# Mobile_Robot_Remote_Controller.net
KiCad netlist of a schematic drawn in Altium Designer
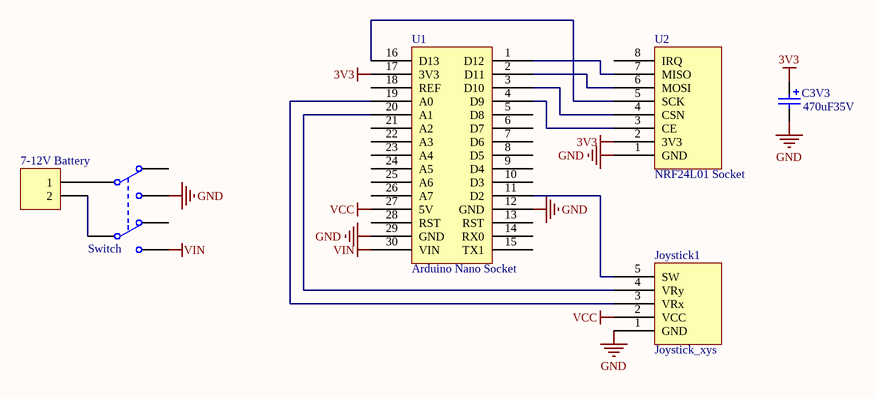
[diagram p0: Mobile Robot Remote Controller.SchDoc]

(export (version "E")
  (design (tool "Eeschema 10.0.6"))
  (components
    (comp (ref "7-12V Battery")
      (value "Header 2")
      (footprint "KF301-2P")
      (libsource (lib "Customer_Library") (part "Header 2"))
    )
    (comp (ref "C3V3")
      (value "470uF35V")
      (footprint "cp10x10")
      (fields (field (name "Comment") "Cap Pol"))
      (libsource (lib "Customer_Library") (part "Cap Pol"))
    )
    (comp (ref "Joystick1")
      (value "Joystick_xys")
      (footprint "Joystick_xys")
      (libsource (lib "Customer_Library") (part "Joystick_xys"))
    )
    (comp (ref "Switch")
      (value "Push Switch")
      (footprint "Push Switch 7x7")
      (libsource (lib "Customer_Library") (part "Push Switch"))
    )
    (comp (ref "U1")
      (value "Arduino Nano Socket")
      (footprint "arduino nano socket")
      (libsource (lib "Customer_Library") (part "Arduino Nano Socket"))
    )
    (comp (ref "U2")
      (value "NRF24L01 Socket")
      (footprint "nrf24l01 socket")
      (libsource (lib "Customer_Library") (part "NRF24L01 Socket"))
    )
  )
  (nets
    (net (code "1") (name "3V3") (class "Default")
      (node (ref "C3V3") (pin "1") (pinfunction "1_1") (pintype "passive"))
      (node (ref "U1") (pin "17") (pinfunction "3V3_17") (pintype "passive"))
      (node (ref "U2") (pin "2") (pinfunction "3V3_2") (pintype "passive"))
    )
    (net (code "2") (name "GND") (class "Default")
      (node (ref "C3V3") (pin "2") (pinfunction "2_2") (pintype "passive"))
      (node (ref "Joystick1") (pin "1") (pinfunction "GND_1") (pintype "passive"))
      (node (ref "Switch") (pin "3") (pinfunction "NO1_3") (pintype "passive"))
      (node (ref "U1") (pin "12") (pinfunction "GND_12") (pintype "passive"))
      (node (ref "U1") (pin "29") (pinfunction "GND_29") (pintype "passive"))
      (node (ref "U2") (pin "1") (pinfunction "GND_1") (pintype "passive"))
    )
    (net (code "3") (name "Net-(Joystick1-SW)") (class "Default")
      (node (ref "Joystick1") (pin "5") (pinfunction "SW_5") (pintype "passive"))
      (node (ref "U1") (pin "11") (pinfunction "D2_11") (pintype "passive"))
    )
    (net (code "4") (name "Net-(Joystick1-VRx)") (class "Default")
      (node (ref "Joystick1") (pin "3") (pinfunction "VRx_3") (pintype "passive"))
      (node (ref "U1") (pin "19") (pinfunction "A0_19") (pintype "passive"))
    )
    (net (code "5") (name "Net-(Joystick1-VRy)") (class "Default")
      (node (ref "Joystick1") (pin "4") (pinfunction "VRy_4") (pintype "passive"))
      (node (ref "U1") (pin "20") (pinfunction "A1_20") (pintype "passive"))
    )
    (net (code "6") (name "Net-(Switch-COMMON1)") (class "Default")
      (node (ref "7-12V Battery") (pin "1") (pinfunction "1_1") (pintype "passive"))
      (node (ref "Switch") (pin "1") (pinfunction "COMMON1_1") (pintype "passive"))
    )
    (net (code "7") (name "Net-(Switch-COMMON2)") (class "Default")
      (node (ref "7-12V Battery") (pin "2") (pinfunction "2_2") (pintype "passive"))
      (node (ref "Switch") (pin "4") (pinfunction "COMMON2_4") (pintype "passive"))
    )
    (net (code "8") (name "Net-(U1-D9)") (class "Default")
      (node (ref "U1") (pin "4") (pinfunction "D9_4") (pintype "passive"))
      (node (ref "U2") (pin "3") (pinfunction "CE_3") (pintype "passive"))
    )
    (net (code "9") (name "Net-(U1-D10)") (class "Default")
      (node (ref "U1") (pin "3") (pinfunction "D10_3") (pintype "passive"))
      (node (ref "U2") (pin "4") (pinfunction "CSN_4") (pintype "passive"))
    )
    (net (code "10") (name "Net-(U1-D11)") (class "Default")
      (node (ref "U1") (pin "2") (pinfunction "D11_2") (pintype "passive"))
      (node (ref "U2") (pin "6") (pinfunction "MOSI_6") (pintype "passive"))
    )
    (net (code "11") (name "Net-(U1-D12)") (class "Default")
      (node (ref "U1") (pin "1") (pinfunction "D12_1") (pintype "passive"))
      (node (ref "U2") (pin "7") (pinfunction "MISO_7") (pintype "passive"))
    )
    (net (code "12") (name "Net-(U1-D13)") (class "Default")
      (node (ref "U1") (pin "16") (pinfunction "D13_16") (pintype "passive"))
      (node (ref "U2") (pin "5") (pinfunction "SCK_5") (pintype "passive"))
    )
    (net (code "13") (name "VCC") (class "Default")
      (node (ref "Joystick1") (pin "2") (pinfunction "VCC_2") (pintype "passive"))
      (node (ref "U1") (pin "27") (pinfunction "5V_27") (pintype "passive"))
    )
    (net (code "14") (name "VIN") (class "Default")
      (node (ref "Switch") (pin "6") (pinfunction "NO2_6") (pintype "passive"))
      (node (ref "U1") (pin "30") (pinfunction "VIN_30") (pintype "passive"))
    )
    (net (code "15") (name "unconnected-(Switch-NC1-Pad2)") (class "Default")
      (node (ref "Switch") (pin "2") (pinfunction "NC1_2") (pintype "passive"))
    )
    (net (code "16") (name "unconnected-(Switch-NC2-Pad5)") (class "Default")
      (node (ref "Switch") (pin "5") (pinfunction "NC2_5") (pintype "passive"))
    )
    (net (code "17") (name "unconnected-(U1-A2-Pad21)") (class "Default")
      (node (ref "U1") (pin "21") (pinfunction "A2_21") (pintype "passive"))
    )
    (net (code "18") (name "unconnected-(U1-A3-Pad22)") (class "Default")
      (node (ref "U1") (pin "22") (pinfunction "A3_22") (pintype "passive"))
    )
    (net (code "19") (name "unconnected-(U1-A4-Pad23)") (class "Default")
      (node (ref "U1") (pin "23") (pinfunction "A4_23") (pintype "passive"))
    )
    (net (code "20") (name "unconnected-(U1-A5-Pad24)") (class "Default")
      (node (ref "U1") (pin "24") (pinfunction "A5_24") (pintype "passive"))
    )
    (net (code "21") (name "unconnected-(U1-A6-Pad25)") (class "Default")
      (node (ref "U1") (pin "25") (pinfunction "A6_25") (pintype "passive"))
    )
    (net (code "22") (name "unconnected-(U1-A7-Pad26)") (class "Default")
      (node (ref "U1") (pin "26") (pinfunction "A7_26") (pintype "passive"))
    )
    (net (code "23") (name "unconnected-(U1-D3-Pad10)") (class "Default")
      (node (ref "U1") (pin "10") (pinfunction "D3_10") (pintype "passive"))
    )
    (net (code "24") (name "unconnected-(U1-D4-Pad9)") (class "Default")
      (node (ref "U1") (pin "9") (pinfunction "D4_9") (pintype "passive"))
    )
    (net (code "25") (name "unconnected-(U1-D5-Pad8)") (class "Default")
      (node (ref "U1") (pin "8") (pinfunction "D5_8") (pintype "passive"))
    )
    (net (code "26") (name "unconnected-(U1-D6-Pad7)") (class "Default")
      (node (ref "U1") (pin "7") (pinfunction "D6_7") (pintype "passive"))
    )
    (net (code "27") (name "unconnected-(U1-D7-Pad6)") (class "Default")
      (node (ref "U1") (pin "6") (pinfunction "D7_6") (pintype "passive"))
    )
    (net (code "28") (name "unconnected-(U1-D8-Pad5)") (class "Default")
      (node (ref "U1") (pin "5") (pinfunction "D8_5") (pintype "passive"))
    )
    (net (code "29") (name "unconnected-(U1-REF-Pad18)") (class "Default")
      (node (ref "U1") (pin "18") (pinfunction "REF_18") (pintype "passive"))
    )
    (net (code "30") (name "unconnected-(U1-RST-Pad13)") (class "Default")
      (node (ref "U1") (pin "13") (pinfunction "RST_13") (pintype "passive"))
    )
    (net (code "31") (name "unconnected-(U1-RST-Pad28)") (class "Default")
      (node (ref "U1") (pin "28") (pinfunction "RST_28") (pintype "passive"))
    )
    (net (code "32") (name "unconnected-(U1-RX0-Pad14)") (class "Default")
      (node (ref "U1") (pin "14") (pinfunction "RX0_14") (pintype "passive"))
    )
    (net (code "33") (name "unconnected-(U1-TX1-Pad15)") (class "Default")
      (node (ref "U1") (pin "15") (pinfunction "TX1_15") (pintype "passive"))
    )
    (net (code "34") (name "unconnected-(U2-IRQ-Pad8)") (class "Default")
      (node (ref "U2") (pin "8") (pinfunction "IRQ_8") (pintype "passive"))
    )
  )
)
